# SCH_AP_tempboard_2024-01-17.net
KiCad netlist of a schematic drawn in EasyEDA
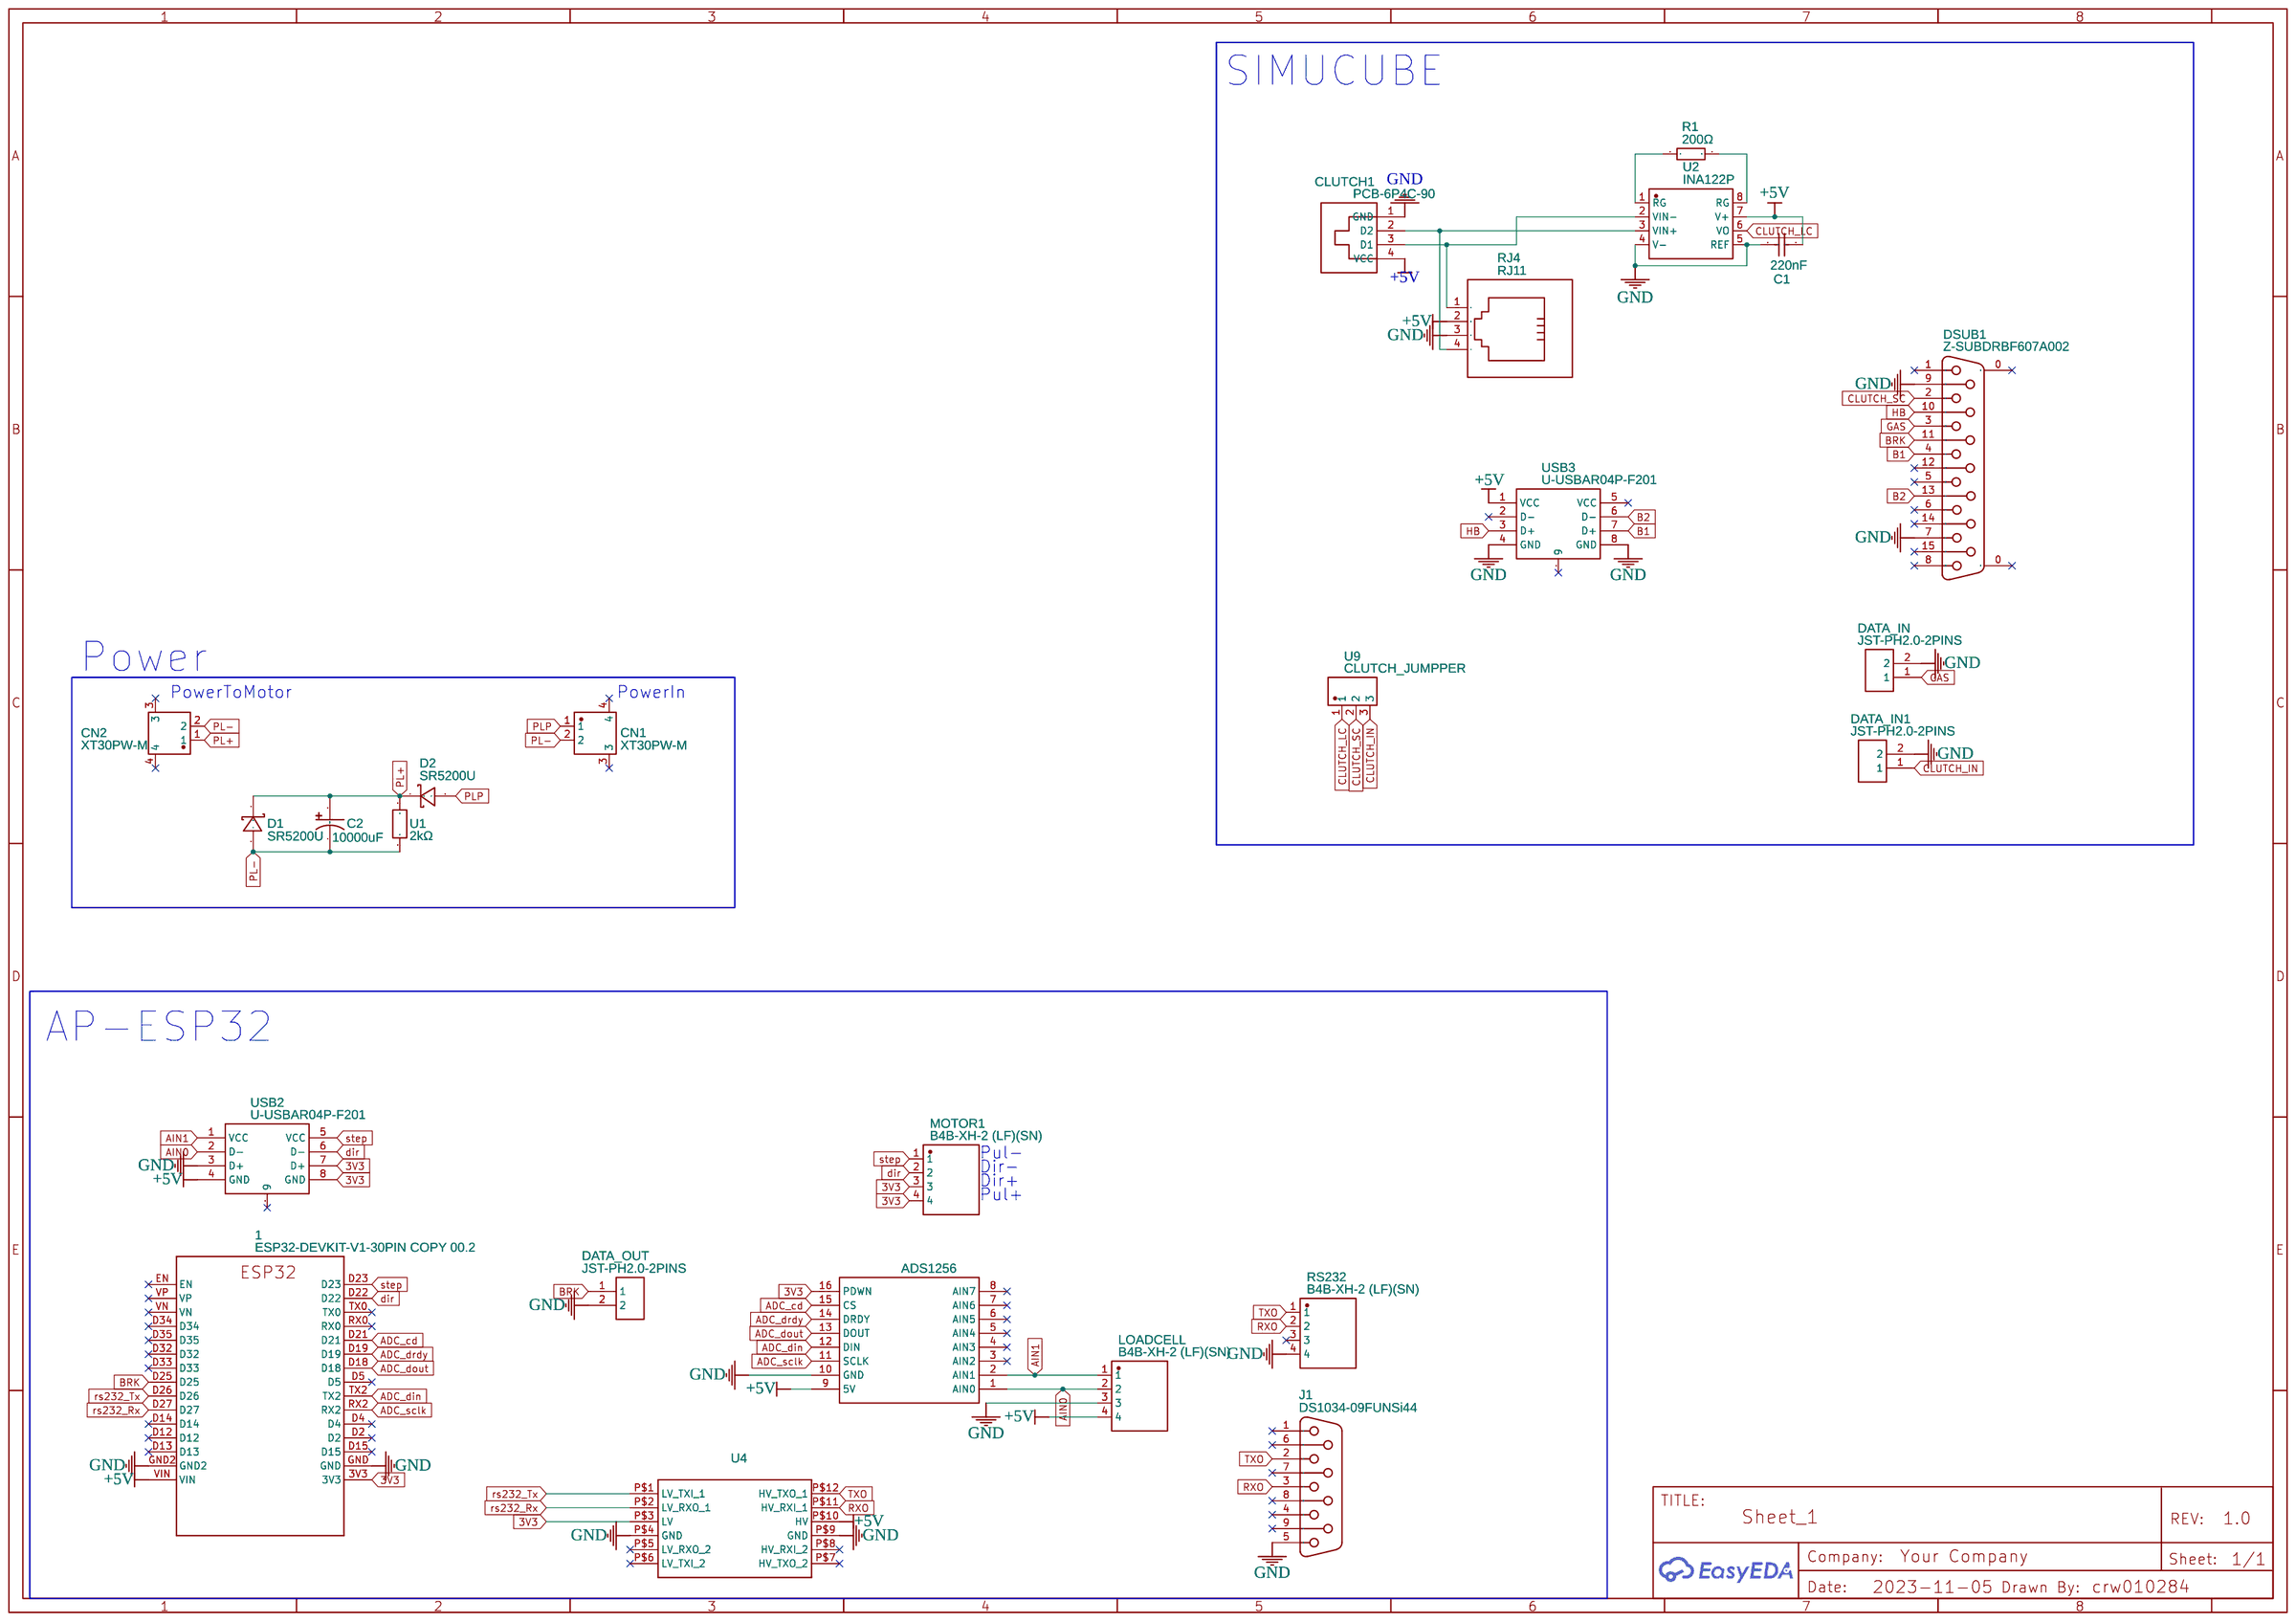
[diagram p0: schematic sheet]

(export (version "E")
  (design (tool "Eeschema 10.0.6"))
  (components
    (comp (ref "1")
      (value "ESP32-DEVKIT-V1-30PIN COPY 00.2")
      (libsource (lib "") (part "ESP32-DEVKIT-V1-30PIN"))
    )
    (comp (ref "C1")
      (value "220nF")
      (fields
        (field (name "Manufacturer Part") "CL10B224KA8NNNC")
        (field (name "Manufacturer") "SAMSUNG(三星)")
      )
      (libsource (lib "") (part "CL10B224KA8NNNC"))
    )
    (comp (ref "C2")
      (value "10000uF")
      (fields (field (name "Manufacturer Part") "HL103M063O510A") (field (name "Manufacturer") "CapXon(丰宾)"))
      (libsource (lib "") (part "HL103M063O510A"))
    )
    (comp (ref "CLUTCH1")
      (value "PCB-6P4C-90")
      (fields (field (name "Manufacturer Part") "R-RJ11R04P-A800") (field (name "Manufacturer") "Ckmtw(灿科盟)"))
      (libsource (lib "") (part "PCB-6P4C-90"))
    )
    (comp (ref "CN1")
      (value "XT30PW-M")
      (fields (field (name "Manufacturer") "AMASS(艾迈斯)"))
      (libsource (lib "") (part "XT30PW-M"))
    )
    (comp (ref "CN2")
      (value "XT30PW-M")
      (fields (field (name "Manufacturer") "AMASS(艾迈斯)"))
      (libsource (lib "") (part "XT30PW-M_1"))
    )
    (comp (ref "D1")
      (value "SR5200U")
      (fields (field (name "Manufacturer") "迪一"))
      (libsource (lib "") (part "SR5200U"))
    )
    (comp (ref "D2")
      (value "SR5200U")
      (fields (field (name "Manufacturer") "迪一"))
      (libsource (lib "") (part "SR5200U_1"))
    )
    (comp (ref "DATA_IN") (value "JST-PH2.0-2PINS") (libsource (lib "") (part "JST-PH2.0-2PINS")))
    (comp (ref "DATA_IN1") (value "JST-PH2.0-2PINS") (libsource (lib "") (part "JST-PH2.0-2PINS")))
    (comp (ref "DATA_OUT") (value "JST-PH2.0-2PINS") (libsource (lib "") (part "JST-PH2.0-2PINS_1")))
    (comp (ref "DSUB1")
      (value "Z-SUBDRBF607A002")
      (fields (field (name "Manufacturer") "Nextron(台湾正凌)"))
      (libsource (lib "") (part "Z-SUBDRBF607A002"))
    )
    (comp (ref "J1")
      (value "DS1034-09FUNSi44")
      (fields (field (name "Manufacturer") "CONNFLY"))
      (libsource (lib "") (part "DS1034-09FUNSi44"))
    )
    (comp (ref "LOADCELL")
      (value "B4B-XH-2 (LF)(SN)")
      (fields (field (name "Manufacturer Part") "B4B-XH-2(LF)(SN)") (field (name "Manufacturer") "JST"))
      (libsource (lib "") (part "B4B-XH-2 (LF)(SN)_2"))
    )
    (comp (ref "MOTOR1")
      (value "B4B-XH-2 (LF)(SN)")
      (fields (field (name "Manufacturer Part") "B4B-XH-2(LF)(SN)") (field (name "Manufacturer") "JST"))
      (libsource (lib "") (part "B4B-XH-2 (LF)(SN)_1"))
    )
    (comp (ref "R1")
      (value "200Ω")
      (fields
        (field (name "Manufacturer Part") "0402WGF2000TCE")
        (field (name "Manufacturer") "UNI-ROYAL(厚声)")
      )
      (libsource (lib "") (part "0402WGF2000TCE"))
    )
    (comp (ref "RJ4")
      (value "RJ11")
      (fields
        (field (name "Manufacturer Part") "RJII-623K-4P4CGray boundless")
        (field (name "Manufacturer") "ReliaPro")
      )
      (libsource (lib "") (part "RJII-623K-4P4CGray boundless"))
    )
    (comp (ref "RS232")
      (value "B4B-XH-2 (LF)(SN)")
      (fields (field (name "Manufacturer Part") "B4B-XH-2(LF)(SN)") (field (name "Manufacturer") "JST"))
      (libsource (lib "") (part "B4B-XH-2 (LF)(SN)"))
    )
    (comp (ref "U1")
      (value "2kΩ")
      (fields (field (name "Manufacturer Part") "RSF5WSJB-91-2K") (field (name "Manufacturer") "YAGEO(国巨)"))
      (libsource (lib "") (part "RSF5WSJB-91-2K"))
    )
    (comp (ref "U2")
      (value "INA122P")
      (fields (field (name "Manufacturer") "TI(德州仪器)"))
      (libsource (lib "") (part "INA122P"))
    )
    (comp (ref "U3") (value "ADS1256") (libsource (lib "") (part "ADS1256")))
    (comp (ref "U4") (value "NO") (libsource (lib "") (part "LOGIC_LEVEL_CONVERTER")))
    (comp (ref "U9")
      (value "CLUTCH_JUMPPER")
      (fields (field (name "Manufacturer Part") "Jumper3"))
      (libsource (lib "") (part "JUMPER3"))
    )
    (comp (ref "USB2")
      (value "U-USBAR04P-F201")
      (fields (field (name "Manufacturer") "Ckmtw(灿科盟)"))
      (libsource (lib "") (part "U-USBAR04P-F201"))
    )
    (comp (ref "USB3")
      (value "U-USBAR04P-F201")
      (fields (field (name "Manufacturer") "Ckmtw(灿科盟)"))
      (libsource (lib "") (part "U-USBAR04P-F201"))
    )
  )
  (nets
    (net (code "1") (name "+5V") (class "Default")
      (node (ref "1") (pin "VIN") (pinfunction "VIN_VIN") (pintype "unspecified"))
      (node (ref "C1") (pin "2") (pinfunction "2_2") (pintype "input"))
      (node (ref "CLUTCH1") (pin "4") (pinfunction "VCC_4") (pintype "unspecified"))
      (node (ref "LOADCELL") (pin "4") (pinfunction "4_4") (pintype "unspecified"))
      (node (ref "RJ4") (pin "2") (pinfunction "2_2") (pintype "unspecified"))
      (node (ref "U2") (pin "7") (pinfunction "V+_7") (pintype "unspecified"))
      (node (ref "U3") (pin "9") (pinfunction "5V_9") (pintype "unspecified"))
      (node (ref "U4") (pin "P$10") (pinfunction "HV_P$10") (pintype "unspecified"))
      (node (ref "USB2") (pin "4") (pinfunction "GND_4") (pintype "unspecified"))
      (node (ref "USB3") (pin "1") (pinfunction "VCC_1") (pintype "unspecified"))
    )
    (net (code "2") (name "3V3") (class "Default")
      (node (ref "1") (pin "3V3") (pinfunction "3V3_3V3") (pintype "unspecified"))
      (node (ref "MOTOR1") (pin "3") (pinfunction "3_3") (pintype "unspecified"))
      (node (ref "MOTOR1") (pin "4") (pinfunction "4_4") (pintype "unspecified"))
      (node (ref "U3") (pin "16") (pinfunction "PDWN_16") (pintype "unspecified"))
      (node (ref "U4") (pin "P$3") (pinfunction "LV_P$3") (pintype "unspecified"))
      (node (ref "USB2") (pin "7") (pinfunction "D+_7") (pintype "unspecified"))
      (node (ref "USB2") (pin "8") (pinfunction "GND_8") (pintype "unspecified"))
    )
    (net (code "3") (name "ADC_cd") (class "Default")
      (node (ref "1") (pin "D21") (pinfunction "D21_D21") (pintype "unspecified"))
      (node (ref "U3") (pin "15") (pinfunction "CS_15") (pintype "unspecified"))
    )
    (net (code "4") (name "ADC_din") (class "Default")
      (node (ref "1") (pin "TX2") (pinfunction "TX2_TX2") (pintype "unspecified"))
      (node (ref "U3") (pin "12") (pinfunction "DIN_12") (pintype "unspecified"))
    )
    (net (code "5") (name "ADC_dout") (class "Default")
      (node (ref "1") (pin "D18") (pinfunction "D18_D18") (pintype "unspecified"))
      (node (ref "U3") (pin "13") (pinfunction "DOUT_13") (pintype "unspecified"))
    )
    (net (code "6") (name "ADC_drdy") (class "Default")
      (node (ref "1") (pin "D19") (pinfunction "D19_D19") (pintype "unspecified"))
      (node (ref "U3") (pin "14") (pinfunction "DRDY_14") (pintype "unspecified"))
    )
    (net (code "7") (name "ADC_sclk") (class "Default")
      (node (ref "1") (pin "RX2") (pinfunction "RX2_RX2") (pintype "unspecified"))
      (node (ref "U3") (pin "11") (pinfunction "SCLK_11") (pintype "unspecified"))
    )
    (net (code "8") (name "AIN0") (class "Default")
      (node (ref "LOADCELL") (pin "2") (pinfunction "2_2") (pintype "unspecified"))
      (node (ref "U3") (pin "1") (pinfunction "AIN0_1") (pintype "unspecified"))
      (node (ref "USB2") (pin "2") (pinfunction "D-_2") (pintype "unspecified"))
    )
    (net (code "9") (name "AIN1") (class "Default")
      (node (ref "LOADCELL") (pin "1") (pinfunction "1_1") (pintype "unspecified"))
      (node (ref "U3") (pin "2") (pinfunction "AIN1_2") (pintype "unspecified"))
      (node (ref "USB2") (pin "1") (pinfunction "VCC_1") (pintype "unspecified"))
    )
    (net (code "10") (name "B1") (class "Default")
      (node (ref "DSUB1") (pin "4") (pinfunction "4_4") (pintype "input"))
      (node (ref "USB3") (pin "7") (pinfunction "D+_7") (pintype "unspecified"))
    )
    (net (code "11") (name "B2") (class "Default")
      (node (ref "DSUB1") (pin "13") (pinfunction "13_13") (pintype "input"))
      (node (ref "USB3") (pin "6") (pinfunction "D-_6") (pintype "unspecified"))
    )
    (net (code "12") (name "BRK") (class "Default")
      (node (ref "1") (pin "D25") (pinfunction "D25_D25") (pintype "unspecified"))
      (node (ref "DATA_OUT") (pin "1") (pinfunction "1_1") (pintype "unspecified"))
      (node (ref "DSUB1") (pin "11") (pinfunction "11_11") (pintype "input"))
    )
    (net (code "13") (name "CLUTCH_IN") (class "Default")
      (node (ref "DATA_IN1") (pin "1") (pinfunction "1_1") (pintype "unspecified"))
      (node (ref "U9") (pin "3") (pinfunction "3_3") (pintype "unspecified"))
    )
    (net (code "14") (name "CLUTCH_LC") (class "Default")
      (node (ref "U2") (pin "6") (pinfunction "VO_6") (pintype "unspecified"))
      (node (ref "U9") (pin "1") (pinfunction "1_1") (pintype "unspecified"))
    )
    (net (code "15") (name "CLUTCH_SC") (class "Default")
      (node (ref "DSUB1") (pin "2") (pinfunction "2_2") (pintype "input"))
      (node (ref "U9") (pin "2") (pinfunction "2_2") (pintype "unspecified"))
    )
    (net (code "16") (name "GAS") (class "Default")
      (node (ref "DATA_IN") (pin "1") (pinfunction "1_1") (pintype "unspecified"))
      (node (ref "DSUB1") (pin "3") (pinfunction "3_3") (pintype "input"))
    )
    (net (code "17") (name "GND") (class "Default")
      (node (ref "1") (pin "GND") (pinfunction "GND_GND") (pintype "unspecified"))
      (node (ref "1") (pin "GND2") (pinfunction "GND2_GND2") (pintype "unspecified"))
      (node (ref "C1") (pin "1") (pinfunction "1_1") (pintype "input"))
      (node (ref "CLUTCH1") (pin "1") (pinfunction "GND_1") (pintype "unspecified"))
      (node (ref "DATA_IN") (pin "2") (pinfunction "2_2") (pintype "unspecified"))
      (node (ref "DATA_IN1") (pin "2") (pinfunction "2_2") (pintype "unspecified"))
      (node (ref "DATA_OUT") (pin "2") (pinfunction "2_2") (pintype "unspecified"))
      (node (ref "DSUB1") (pin "7") (pinfunction "7_7") (pintype "input"))
      (node (ref "DSUB1") (pin "9") (pinfunction "9_9") (pintype "input"))
      (node (ref "J1") (pin "5") (pinfunction "5_5") (pintype "unspecified"))
      (node (ref "LOADCELL") (pin "3") (pinfunction "3_3") (pintype "unspecified"))
      (node (ref "RJ4") (pin "3") (pinfunction "3_3") (pintype "unspecified"))
      (node (ref "RS232") (pin "4") (pinfunction "4_4") (pintype "unspecified"))
      (node (ref "U2") (pin "4") (pinfunction "V-_4") (pintype "unspecified"))
      (node (ref "U2") (pin "5") (pinfunction "REF_5") (pintype "unspecified"))
      (node (ref "U3") (pin "10") (pinfunction "GND_10") (pintype "unspecified"))
      (node (ref "U4") (pin "P$4") (pinfunction "GND_P$4") (pintype "unspecified"))
      (node (ref "U4") (pin "P$9") (pinfunction "GND_P$9") (pintype "unspecified"))
      (node (ref "USB2") (pin "3") (pinfunction "D+_3") (pintype "unspecified"))
      (node (ref "USB3") (pin "4") (pinfunction "GND_4") (pintype "unspecified"))
      (node (ref "USB3") (pin "8") (pinfunction "GND_8") (pintype "unspecified"))
    )
    (net (code "18") (name "HB") (class "Default")
      (node (ref "DSUB1") (pin "10") (pinfunction "10_10") (pintype "input"))
      (node (ref "USB3") (pin "3") (pinfunction "D+_3") (pintype "unspecified"))
    )
    (net (code "19") (name "Net-(CLUTCH1-D1)") (class "Default")
      (node (ref "CLUTCH1") (pin "3") (pinfunction "D1_3") (pintype "unspecified"))
      (node (ref "RJ4") (pin "1") (pinfunction "1_1") (pintype "unspecified"))
      (node (ref "U2") (pin "2") (pinfunction "VIN-_2") (pintype "unspecified"))
    )
    (net (code "20") (name "Net-(CLUTCH1-D2)") (class "Default")
      (node (ref "CLUTCH1") (pin "2") (pinfunction "D2_2") (pintype "unspecified"))
      (node (ref "RJ4") (pin "4") (pinfunction "4_4") (pintype "unspecified"))
      (node (ref "U2") (pin "3") (pinfunction "VIN+_3") (pintype "unspecified"))
    )
    (net (code "21") (name "Net-(R1-Pad1)") (class "Default")
      (node (ref "R1") (pin "1") (pinfunction "1_1") (pintype "input"))
      (node (ref "U2") (pin "1") (pinfunction "RG_1") (pintype "unspecified"))
    )
    (net (code "22") (name "Net-(R1-Pad2)") (class "Default")
      (node (ref "R1") (pin "2") (pinfunction "2_2") (pintype "input"))
      (node (ref "U2") (pin "8") (pinfunction "RG_8") (pintype "unspecified"))
    )
    (net (code "23") (name "PL+") (class "Default")
      (node (ref "C2") (pin "1") (pinfunction "1_1") (pintype "unspecified"))
      (node (ref "CN2") (pin "1") (pinfunction "1_1") (pintype "unspecified"))
      (node (ref "D1") (pin "1") (pinfunction "C_1") (pintype "unspecified"))
      (node (ref "D2") (pin "1") (pinfunction "C_1") (pintype "unspecified"))
      (node (ref "U1") (pin "1") (pinfunction "1_1") (pintype "unspecified"))
    )
    (net (code "24") (name "PL-") (class "Default")
      (node (ref "C2") (pin "2") (pinfunction "2_2") (pintype "unspecified"))
      (node (ref "CN1") (pin "2") (pinfunction "2_2") (pintype "unspecified"))
      (node (ref "CN2") (pin "2") (pinfunction "2_2") (pintype "unspecified"))
      (node (ref "D1") (pin "2") (pinfunction "A_2") (pintype "unspecified"))
      (node (ref "U1") (pin "2") (pinfunction "2_2") (pintype "unspecified"))
    )
    (net (code "25") (name "PLP") (class "Default")
      (node (ref "CN1") (pin "1") (pinfunction "1_1") (pintype "unspecified"))
      (node (ref "D2") (pin "2") (pinfunction "A_2") (pintype "unspecified"))
    )
    (net (code "26") (name "RXO") (class "Default")
      (node (ref "J1") (pin "3") (pinfunction "3_3") (pintype "unspecified"))
      (node (ref "RS232") (pin "2") (pinfunction "2_2") (pintype "unspecified"))
      (node (ref "U4") (pin "P$11") (pinfunction "HV_RXI_1_P$11") (pintype "unspecified"))
    )
    (net (code "27") (name "TXO") (class "Default")
      (node (ref "J1") (pin "2") (pinfunction "2_2") (pintype "unspecified"))
      (node (ref "RS232") (pin "1") (pinfunction "1_1") (pintype "unspecified"))
      (node (ref "U4") (pin "P$12") (pinfunction "HV_TXO_1_P$12") (pintype "unspecified"))
    )
    (net (code "28") (name "dir") (class "Default")
      (node (ref "1") (pin "D22") (pinfunction "D22_D22") (pintype "unspecified"))
      (node (ref "MOTOR1") (pin "2") (pinfunction "2_2") (pintype "unspecified"))
      (node (ref "USB2") (pin "6") (pinfunction "D-_6") (pintype "unspecified"))
    )
    (net (code "29") (name "rs232_Rx") (class "Default")
      (node (ref "1") (pin "D27") (pinfunction "D27_D27") (pintype "unspecified"))
      (node (ref "U4") (pin "P$2") (pinfunction "LV_RXO_1_P$2") (pintype "unspecified"))
    )
    (net (code "30") (name "rs232_Tx") (class "Default")
      (node (ref "1") (pin "D26") (pinfunction "D26_D26") (pintype "unspecified"))
      (node (ref "U4") (pin "P$1") (pinfunction "LV_TXI_1_P$1") (pintype "unspecified"))
    )
    (net (code "31") (name "step") (class "Default")
      (node (ref "1") (pin "D23") (pinfunction "D23_D23") (pintype "unspecified"))
      (node (ref "MOTOR1") (pin "1") (pinfunction "1_1") (pintype "unspecified"))
      (node (ref "USB2") (pin "5") (pinfunction "VCC_5") (pintype "unspecified"))
    )
    (net (code "32") (name "unconnected-(1-PadD2)") (class "Default")
      (node (ref "1") (pin "D2") (pinfunction "D2_D2") (pintype "unspecified+no_connect"))
    )
    (net (code "33") (name "unconnected-(1-PadD4)") (class "Default")
      (node (ref "1") (pin "D4") (pinfunction "D4_D4") (pintype "unspecified+no_connect"))
    )
    (net (code "34") (name "unconnected-(1-PadD5)") (class "Default")
      (node (ref "1") (pin "D5") (pinfunction "D5_D5") (pintype "unspecified+no_connect"))
    )
    (net (code "35") (name "unconnected-(1-PadD12)") (class "Default")
      (node (ref "1") (pin "D12") (pinfunction "D12_D12") (pintype "unspecified+no_connect"))
    )
    (net (code "36") (name "unconnected-(1-PadD13)") (class "Default")
      (node (ref "1") (pin "D13") (pinfunction "D13_D13") (pintype "unspecified+no_connect"))
    )
    (net (code "37") (name "unconnected-(1-PadD14)") (class "Default")
      (node (ref "1") (pin "D14") (pinfunction "D14_D14") (pintype "unspecified+no_connect"))
    )
    (net (code "38") (name "unconnected-(1-PadD15)") (class "Default")
      (node (ref "1") (pin "D15") (pinfunction "D15_D15") (pintype "unspecified+no_connect"))
    )
    (net (code "39") (name "unconnected-(1-PadD32)") (class "Default")
      (node (ref "1") (pin "D32") (pinfunction "D32_D32") (pintype "unspecified+no_connect"))
    )
    (net (code "40") (name "unconnected-(1-PadD33)") (class "Default")
      (node (ref "1") (pin "D33") (pinfunction "D33_D33") (pintype "unspecified+no_connect"))
    )
    (net (code "41") (name "unconnected-(1-PadD34)") (class "Default")
      (node (ref "1") (pin "D34") (pinfunction "D34_D34") (pintype "unspecified+no_connect"))
    )
    (net (code "42") (name "unconnected-(1-PadD35)") (class "Default")
      (node (ref "1") (pin "D35") (pinfunction "D35_D35") (pintype "unspecified+no_connect"))
    )
    (net (code "43") (name "unconnected-(1-PadEN)") (class "Default")
      (node (ref "1") (pin "EN") (pinfunction "EN_EN") (pintype "unspecified+no_connect"))
    )
    (net (code "44") (name "unconnected-(1-PadRX0)") (class "Default")
      (node (ref "1") (pin "RX0") (pinfunction "RX0_RX0") (pintype "unspecified+no_connect"))
    )
    (net (code "45") (name "unconnected-(1-PadTX0)") (class "Default")
      (node (ref "1") (pin "TX0") (pinfunction "TX0_TX0") (pintype "unspecified+no_connect"))
    )
    (net (code "46") (name "unconnected-(1-PadVN)") (class "Default")
      (node (ref "1") (pin "VN") (pinfunction "VN_VN") (pintype "unspecified+no_connect"))
    )
    (net (code "47") (name "unconnected-(1-PadVP)") (class "Default")
      (node (ref "1") (pin "VP") (pinfunction "VP_VP") (pintype "unspecified+no_connect"))
    )
    (net (code "48") (name "unconnected-(CN1-Pad3)") (class "Default")
      (node (ref "CN1") (pin "3") (pinfunction "3_3") (pintype "unspecified+no_connect"))
    )
    (net (code "49") (name "unconnected-(CN1-Pad4)") (class "Default")
      (node (ref "CN1") (pin "4") (pinfunction "4_4") (pintype "unspecified+no_connect"))
    )
    (net (code "50") (name "unconnected-(CN2-Pad3)") (class "Default")
      (node (ref "CN2") (pin "3") (pinfunction "3_3") (pintype "unspecified+no_connect"))
    )
    (net (code "51") (name "unconnected-(CN2-Pad4)") (class "Default")
      (node (ref "CN2") (pin "4") (pinfunction "4_4") (pintype "unspecified+no_connect"))
    )
    (net (code "52") (name "unconnected-(DSUB1-MH1-Pad0)") (class "Default")
      (node (ref "DSUB1") (pin "0") (pinfunction "MH1_0") (pintype "input+no_connect"))
    )
    (net (code "53") (name "unconnected-(DSUB1-MH2-Pad0)") (class "Default")
      (node (ref "DSUB1") (pin "0") (pinfunction "MH2_0") (pintype "input+no_connect"))
    )
    (net (code "54") (name "unconnected-(DSUB1-Pad1)") (class "Default")
      (node (ref "DSUB1") (pin "1") (pinfunction "1_1") (pintype "input+no_connect"))
    )
    (net (code "55") (name "unconnected-(DSUB1-Pad5)") (class "Default")
      (node (ref "DSUB1") (pin "5") (pinfunction "5_5") (pintype "input+no_connect"))
    )
    (net (code "56") (name "unconnected-(DSUB1-Pad6)") (class "Default")
      (node (ref "DSUB1") (pin "6") (pinfunction "6_6") (pintype "input+no_connect"))
    )
    (net (code "57") (name "unconnected-(DSUB1-Pad8)") (class "Default")
      (node (ref "DSUB1") (pin "8") (pinfunction "8_8") (pintype "input+no_connect"))
    )
    (net (code "58") (name "unconnected-(DSUB1-Pad12)") (class "Default")
      (node (ref "DSUB1") (pin "12") (pinfunction "12_12") (pintype "input+no_connect"))
    )
    (net (code "59") (name "unconnected-(DSUB1-Pad14)") (class "Default")
      (node (ref "DSUB1") (pin "14") (pinfunction "14_14") (pintype "input+no_connect"))
    )
    (net (code "60") (name "unconnected-(DSUB1-Pad15)") (class "Default")
      (node (ref "DSUB1") (pin "15") (pinfunction "15_15") (pintype "input+no_connect"))
    )
    (net (code "61") (name "unconnected-(J1-Pad1)") (class "Default")
      (node (ref "J1") (pin "1") (pinfunction "1_1") (pintype "unspecified+no_connect"))
    )
    (net (code "62") (name "unconnected-(J1-Pad4)") (class "Default")
      (node (ref "J1") (pin "4") (pinfunction "4_4") (pintype "unspecified+no_connect"))
    )
    (net (code "63") (name "unconnected-(J1-Pad6)") (class "Default")
      (node (ref "J1") (pin "6") (pinfunction "6_6") (pintype "unspecified+no_connect"))
    )
    (net (code "64") (name "unconnected-(J1-Pad7)") (class "Default")
      (node (ref "J1") (pin "7") (pinfunction "7_7") (pintype "unspecified+no_connect"))
    )
    (net (code "65") (name "unconnected-(J1-Pad8)") (class "Default")
      (node (ref "J1") (pin "8") (pinfunction "8_8") (pintype "unspecified+no_connect"))
    )
    (net (code "66") (name "unconnected-(J1-Pad9)") (class "Default")
      (node (ref "J1") (pin "9") (pinfunction "9_9") (pintype "unspecified+no_connect"))
    )
    (net (code "67") (name "unconnected-(RS232-Pad3)") (class "Default")
      (node (ref "RS232") (pin "3") (pinfunction "3_3") (pintype "unspecified+no_connect"))
    )
    (net (code "68") (name "unconnected-(U3-AIN2-Pad3)") (class "Default")
      (node (ref "U3") (pin "3") (pinfunction "AIN2_3") (pintype "unspecified+no_connect"))
    )
    (net (code "69") (name "unconnected-(U3-AIN3-Pad4)") (class "Default")
      (node (ref "U3") (pin "4") (pinfunction "AIN3_4") (pintype "unspecified+no_connect"))
    )
    (net (code "70") (name "unconnected-(U3-AIN4-Pad5)") (class "Default")
      (node (ref "U3") (pin "5") (pinfunction "AIN4_5") (pintype "unspecified+no_connect"))
    )
    (net (code "71") (name "unconnected-(U3-AIN5-Pad6)") (class "Default")
      (node (ref "U3") (pin "6") (pinfunction "AIN5_6") (pintype "unspecified+no_connect"))
    )
    (net (code "72") (name "unconnected-(U3-AIN6-Pad7)") (class "Default")
      (node (ref "U3") (pin "7") (pinfunction "AIN6_7") (pintype "unspecified+no_connect"))
    )
    (net (code "73") (name "unconnected-(U3-AIN7-Pad8)") (class "Default")
      (node (ref "U3") (pin "8") (pinfunction "AIN7_8") (pintype "unspecified+no_connect"))
    )
    (net (code "74") (name "unconnected-(U4-HV_RXI_2-PadP$8)") (class "Default")
      (node (ref "U4") (pin "P$8") (pinfunction "HV_RXI_2_P$8") (pintype "unspecified+no_connect"))
    )
    (net (code "75") (name "unconnected-(U4-HV_TXO_2-PadP$7)") (class "Default")
      (node (ref "U4") (pin "P$7") (pinfunction "HV_TXO_2_P$7") (pintype "unspecified+no_connect"))
    )
    (net (code "76") (name "unconnected-(U4-LV_RXO_2-PadP$5)") (class "Default")
      (node (ref "U4") (pin "P$5") (pinfunction "LV_RXO_2_P$5") (pintype "unspecified+no_connect"))
    )
    (net (code "77") (name "unconnected-(U4-LV_TXI_2-PadP$6)") (class "Default")
      (node (ref "U4") (pin "P$6") (pinfunction "LV_TXI_2_P$6") (pintype "unspecified+no_connect"))
    )
    (net (code "78") (name "unconnected-(USB2-Pad9)") (class "Default")
      (node (ref "USB2") (pin "9") (pinfunction "9_9") (pintype "unspecified+no_connect"))
    )
    (net (code "79") (name "unconnected-(USB3-D--Pad2)") (class "Default")
      (node (ref "USB3") (pin "2") (pinfunction "D-_2") (pintype "unspecified+no_connect"))
    )
    (net (code "80") (name "unconnected-(USB3-Pad9)") (class "Default")
      (node (ref "USB3") (pin "9") (pinfunction "9_9") (pintype "unspecified+no_connect"))
    )
    (net (code "81") (name "unconnected-(USB3-VCC-Pad5)") (class "Default")
      (node (ref "USB3") (pin "5") (pinfunction "VCC_5") (pintype "unspecified+no_connect"))
    )
  )
)
